# tempeh_NoHat.net
KiCad netlist of a schematic drawn in EAGLE
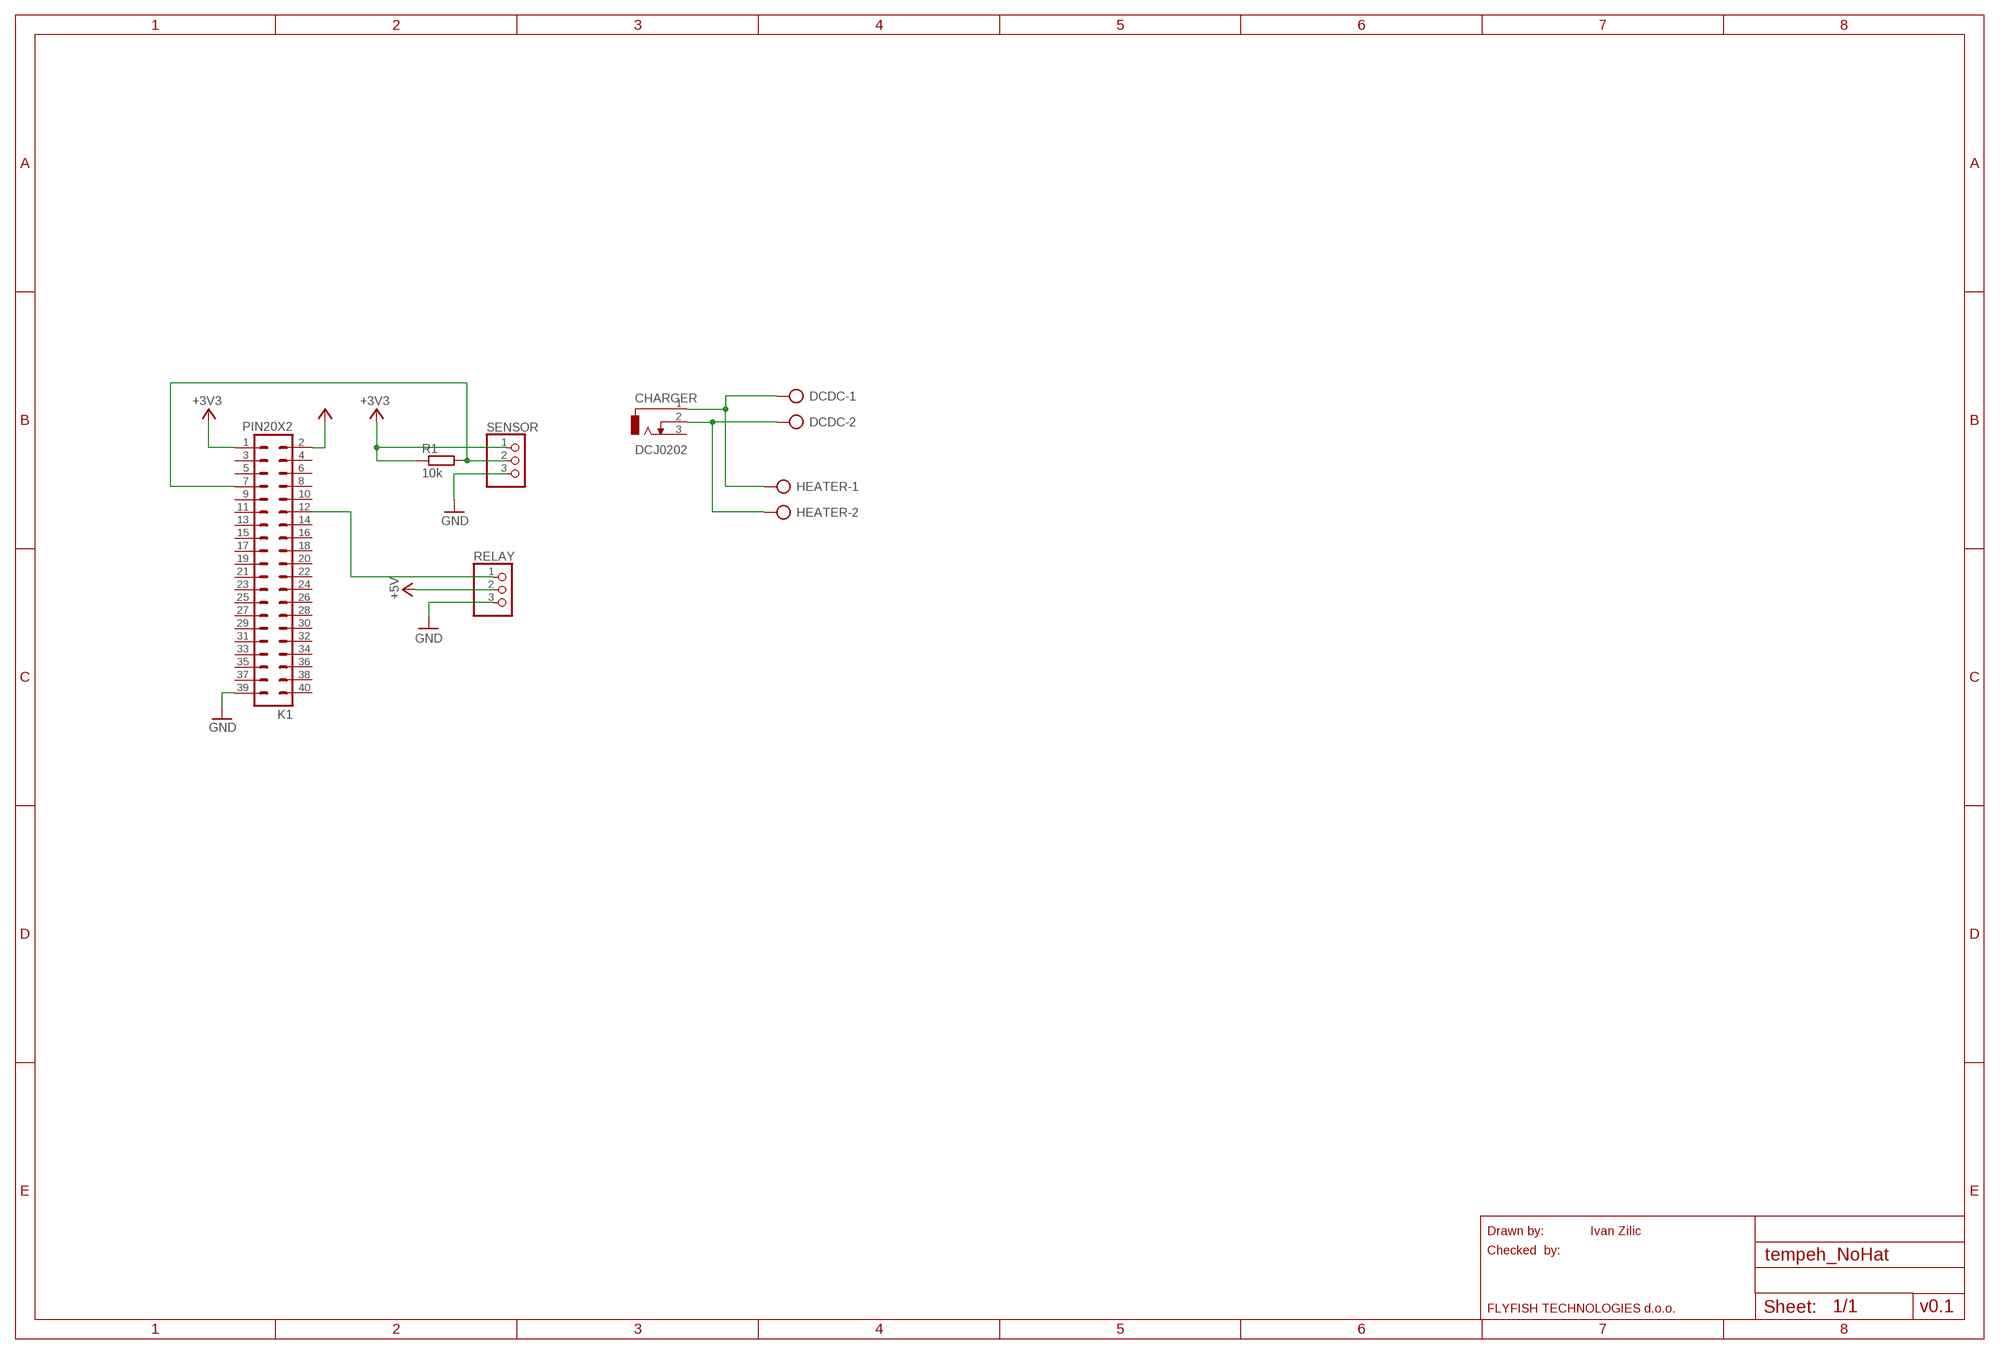
[diagram p0: schematic, sheet 1]

(export (version "E")
  (design (tool "Eeschema 10.0.6"))
  (components
    (comp (ref "CHARGER")
      (value "DCJ0202")
      (footprint "eagle-import:DCJ0202")
      (libsource (lib "eagle-import") (part "DCJ0202"))
    )
    (comp (ref "DCDC")
      (value "AK300/2")
      (footprint "eagle-import:AK300_2")
      (libsource (lib "eagle-import") (part "AK300/2"))
    )
    (comp (ref "HEATER")
      (value "AK300/2")
      (footprint "eagle-import:AK300_2")
      (libsource (lib "eagle-import") (part "AK300/2"))
    )
    (comp (ref "K1")
      (value "PIN20X2")
      (footprint "eagle-import:PIN_20X2")
      (libsource (lib "eagle-import") (part "PIN20X2"))
    )
    (comp (ref "R1")
      (value "10k")
      (footprint "eagle-import:0204_7")
      (libsource (lib "eagle-import") (part "R-EU_0204/7"))
    )
    (comp (ref "RELAY")
      (value "PINHD-1X3")
      (footprint "eagle-import:1X03")
      (libsource (lib "eagle-import") (part "PINHD-1X3"))
    )
    (comp (ref "SENSOR")
      (value "PINHD-1X3")
      (footprint "eagle-import:1X03")
      (libsource (lib "eagle-import") (part "PINHD-1X3"))
    )
  )
  (nets
    (net (code "1") (name "+3V3") (class "Default")
      (node (ref "K1") (pin "1") (pinfunction "1_1") (pintype "passive"))
      (node (ref "R1") (pin "1") (pinfunction "1_1") (pintype "passive"))
      (node (ref "SENSOR") (pin "1") (pinfunction "1_1") (pintype "passive"))
    )
    (net (code "2") (name "+5V") (class "Default")
      (node (ref "K1") (pin "2") (pinfunction "2_2") (pintype "passive"))
      (node (ref "RELAY") (pin "2") (pinfunction "2_2") (pintype "passive"))
    )
    (net (code "3") (name "GND") (class "Default")
      (node (ref "K1") (pin "39") (pinfunction "39_39") (pintype "passive"))
      (node (ref "RELAY") (pin "3") (pinfunction "3_3") (pintype "passive"))
      (node (ref "SENSOR") (pin "3") (pinfunction "3_3") (pintype "passive"))
    )
    (net (code "4") (name "Net-(DCDCA-KL)") (class "Default")
      (node (ref "CHARGER") (pin "1") (pinfunction "1_1") (pintype "passive"))
      (node (ref "DCDC") (pin "1") (pinfunction "KL_1") (pintype "passive"))
      (node (ref "HEATER") (pin "1") (pinfunction "KL_1") (pintype "passive"))
    )
    (net (code "5") (name "Net-(DCDCB-KL)") (class "Default")
      (node (ref "CHARGER") (pin "2") (pinfunction "2_2") (pintype "passive"))
      (node (ref "DCDC") (pin "2") (pinfunction "KL_2") (pintype "passive"))
      (node (ref "HEATER") (pin "2") (pinfunction "KL_2") (pintype "passive"))
    )
    (net (code "6") (name "Net-(K1-Pad7)") (class "Default")
      (node (ref "K1") (pin "7") (pinfunction "7_7") (pintype "passive"))
      (node (ref "R1") (pin "2") (pinfunction "2_2") (pintype "passive"))
      (node (ref "SENSOR") (pin "2") (pinfunction "2_2") (pintype "passive"))
    )
    (net (code "7") (name "Net-(K1-Pad12)") (class "Default")
      (node (ref "K1") (pin "12") (pinfunction "12_12") (pintype "passive"))
      (node (ref "RELAY") (pin "1") (pinfunction "1_1") (pintype "passive"))
    )
    (net (code "8") (name "unconnected-(CHARGER-Pad3)") (class "Default")
      (node (ref "CHARGER") (pin "3") (pinfunction "3_3") (pintype "passive"))
    )
    (net (code "9") (name "unconnected-(K1-Pad3)") (class "Default")
      (node (ref "K1") (pin "3") (pinfunction "3_3") (pintype "passive"))
    )
    (net (code "10") (name "unconnected-(K1-Pad4)") (class "Default")
      (node (ref "K1") (pin "4") (pinfunction "4_4") (pintype "passive"))
    )
    (net (code "11") (name "unconnected-(K1-Pad5)") (class "Default")
      (node (ref "K1") (pin "5") (pinfunction "5_5") (pintype "passive"))
    )
    (net (code "12") (name "unconnected-(K1-Pad6)") (class "Default")
      (node (ref "K1") (pin "6") (pinfunction "6_6") (pintype "passive"))
    )
    (net (code "13") (name "unconnected-(K1-Pad8)") (class "Default")
      (node (ref "K1") (pin "8") (pinfunction "8_8") (pintype "passive"))
    )
    (net (code "14") (name "unconnected-(K1-Pad9)") (class "Default")
      (node (ref "K1") (pin "9") (pinfunction "9_9") (pintype "passive"))
    )
    (net (code "15") (name "unconnected-(K1-Pad10)") (class "Default")
      (node (ref "K1") (pin "10") (pinfunction "10_10") (pintype "passive"))
    )
    (net (code "16") (name "unconnected-(K1-Pad11)") (class "Default")
      (node (ref "K1") (pin "11") (pinfunction "11_11") (pintype "passive"))
    )
    (net (code "17") (name "unconnected-(K1-Pad13)") (class "Default")
      (node (ref "K1") (pin "13") (pinfunction "13_13") (pintype "passive"))
    )
    (net (code "18") (name "unconnected-(K1-Pad14)") (class "Default")
      (node (ref "K1") (pin "14") (pinfunction "14_14") (pintype "passive"))
    )
    (net (code "19") (name "unconnected-(K1-Pad15)") (class "Default")
      (node (ref "K1") (pin "15") (pinfunction "15_15") (pintype "passive"))
    )
    (net (code "20") (name "unconnected-(K1-Pad16)") (class "Default")
      (node (ref "K1") (pin "16") (pinfunction "16_16") (pintype "passive"))
    )
    (net (code "21") (name "unconnected-(K1-Pad17)") (class "Default")
      (node (ref "K1") (pin "17") (pinfunction "17_17") (pintype "passive"))
    )
    (net (code "22") (name "unconnected-(K1-Pad18)") (class "Default")
      (node (ref "K1") (pin "18") (pinfunction "18_18") (pintype "passive"))
    )
    (net (code "23") (name "unconnected-(K1-Pad19)") (class "Default")
      (node (ref "K1") (pin "19") (pinfunction "19_19") (pintype "passive"))
    )
    (net (code "24") (name "unconnected-(K1-Pad20)") (class "Default")
      (node (ref "K1") (pin "20") (pinfunction "20_20") (pintype "passive"))
    )
    (net (code "25") (name "unconnected-(K1-Pad21)") (class "Default")
      (node (ref "K1") (pin "21") (pinfunction "21_21") (pintype "passive"))
    )
    (net (code "26") (name "unconnected-(K1-Pad22)") (class "Default")
      (node (ref "K1") (pin "22") (pinfunction "22_22") (pintype "passive"))
    )
    (net (code "27") (name "unconnected-(K1-Pad23)") (class "Default")
      (node (ref "K1") (pin "23") (pinfunction "23_23") (pintype "passive"))
    )
    (net (code "28") (name "unconnected-(K1-Pad24)") (class "Default")
      (node (ref "K1") (pin "24") (pinfunction "24_24") (pintype "passive"))
    )
    (net (code "29") (name "unconnected-(K1-Pad25)") (class "Default")
      (node (ref "K1") (pin "25") (pinfunction "25_25") (pintype "passive"))
    )
    (net (code "30") (name "unconnected-(K1-Pad26)") (class "Default")
      (node (ref "K1") (pin "26") (pinfunction "26_26") (pintype "passive"))
    )
    (net (code "31") (name "unconnected-(K1-Pad27)") (class "Default")
      (node (ref "K1") (pin "27") (pinfunction "27_27") (pintype "passive"))
    )
    (net (code "32") (name "unconnected-(K1-Pad28)") (class "Default")
      (node (ref "K1") (pin "28") (pinfunction "28_28") (pintype "passive"))
    )
    (net (code "33") (name "unconnected-(K1-Pad29)") (class "Default")
      (node (ref "K1") (pin "29") (pinfunction "29_29") (pintype "passive"))
    )
    (net (code "34") (name "unconnected-(K1-Pad30)") (class "Default")
      (node (ref "K1") (pin "30") (pinfunction "30_30") (pintype "passive"))
    )
    (net (code "35") (name "unconnected-(K1-Pad31)") (class "Default")
      (node (ref "K1") (pin "31") (pinfunction "31_31") (pintype "passive"))
    )
    (net (code "36") (name "unconnected-(K1-Pad32)") (class "Default")
      (node (ref "K1") (pin "32") (pinfunction "32_32") (pintype "passive"))
    )
    (net (code "37") (name "unconnected-(K1-Pad33)") (class "Default")
      (node (ref "K1") (pin "33") (pinfunction "33_33") (pintype "passive"))
    )
    (net (code "38") (name "unconnected-(K1-Pad34)") (class "Default")
      (node (ref "K1") (pin "34") (pinfunction "34_34") (pintype "passive"))
    )
    (net (code "39") (name "unconnected-(K1-Pad35)") (class "Default")
      (node (ref "K1") (pin "35") (pinfunction "35_35") (pintype "passive"))
    )
    (net (code "40") (name "unconnected-(K1-Pad36)") (class "Default")
      (node (ref "K1") (pin "36") (pinfunction "36_36") (pintype "passive"))
    )
    (net (code "41") (name "unconnected-(K1-Pad37)") (class "Default")
      (node (ref "K1") (pin "37") (pinfunction "37_37") (pintype "passive"))
    )
    (net (code "42") (name "unconnected-(K1-Pad38)") (class "Default")
      (node (ref "K1") (pin "38") (pinfunction "38_38") (pintype "passive"))
    )
    (net (code "43") (name "unconnected-(K1-Pad40)") (class "Default")
      (node (ref "K1") (pin "40") (pinfunction "40_40") (pintype "passive"))
    )
  )
)
